# ANEMOMETRO_REED_SWITCH.net
KiCad netlist of a schematic drawn in EAGLE
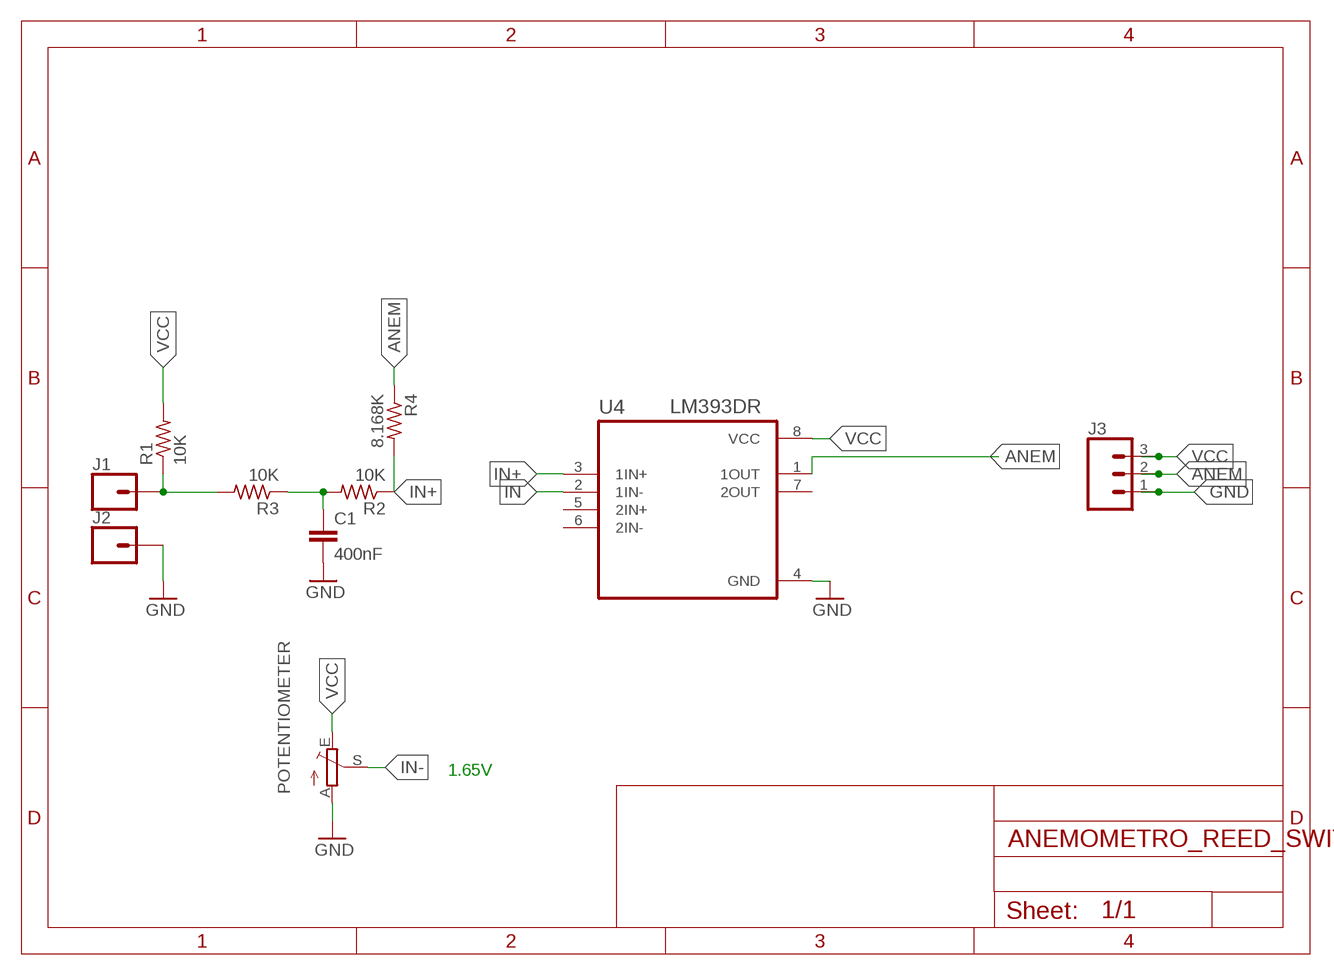
[diagram p0: schematic, sheet 1]

(export (version "E")
  (design (tool "Eeschema 10.0.6"))
  (components
    (comp (ref "C1")
      (value "400nF")
      (footprint "eagle-import:C0603")
      (libsource (lib "eagle-import") (part "C-EUC0603"))
    )
    (comp (ref "J1")
      (value "CONN_01PTH_NO_SILK_YES_STOP")
      (footprint "eagle-import:1X01_NO_SILK")
      (libsource (lib "eagle-import") (part "CONN_01PTH_NO_SILK_YES_STOP"))
    )
    (comp (ref "J2")
      (value "CONN_01PTH_NO_SILK_YES_STOP")
      (footprint "eagle-import:1X01_NO_SILK")
      (libsource (lib "eagle-import") (part "CONN_01PTH_NO_SILK_YES_STOP"))
    )
    (comp (ref "J3")
      (value "CONN_03JST-PTH-VERT")
      (footprint "eagle-import:JST-3-PTH-VERT")
      (libsource (lib "eagle-import") (part "CONN_03JST-PTH-VERT"))
    )
    (comp (ref "POTENTIOMETER")
      (value "TRIM_EU-S64W")
      (footprint "eagle-import:S64W")
      (libsource (lib "eagle-import") (part "TRIM_EU-S64W"))
    )
    (comp (ref "R1")
      (value "10K")
      (footprint "eagle-import:R0603")
      (libsource (lib "eagle-import") (part "R-US_R0603"))
    )
    (comp (ref "R2")
      (value "10K")
      (footprint "eagle-import:R0603")
      (libsource (lib "eagle-import") (part "R-US_R0603"))
    )
    (comp (ref "R3")
      (value "10K")
      (footprint "eagle-import:R0603")
      (libsource (lib "eagle-import") (part "R-US_R0603"))
    )
    (comp (ref "R4")
      (value "8.168K")
      (footprint "eagle-import:R0603")
      (libsource (lib "eagle-import") (part "R-US_R0603"))
    )
    (comp (ref "U4")
      (value "LM393DR")
      (footprint "eagle-import:SOIC127P599X175-8N")
      (fields (field (name "MF") "Texas Instruments"))
      (libsource (lib "eagle-import") (part "LM393DR"))
    )
  )
  (nets
    (net (code "1") (name "ANEM") (class "Default")
      (node (ref "J3") (pin "2") (pinfunction "2_2") (pintype "passive"))
      (node (ref "R4") (pin "1") (pinfunction "1_1") (pintype "passive"))
      (node (ref "U4") (pin "1") (pinfunction "1OUT_1") (pintype "output"))
    )
    (net (code "2") (name "GND") (class "Default")
      (node (ref "C1") (pin "2") (pinfunction "2_2") (pintype "passive"))
      (node (ref "J2") (pin "1") (pinfunction "1_1") (pintype "passive"))
      (node (ref "J3") (pin "1") (pinfunction "1_1") (pintype "passive"))
      (node (ref "POTENTIOMETER") (pin "A") (pinfunction "A_A") (pintype "passive"))
      (node (ref "U4") (pin "4") (pinfunction "GND_4") (pintype "power_in"))
    )
    (net (code "3") (name "IN") (class "Default")
      (node (ref "U4") (pin "2") (pinfunction "1IN-_2") (pintype "input"))
    )
    (net (code "4") (name "IN+") (class "Default")
      (node (ref "R2") (pin "1") (pinfunction "1_1") (pintype "passive"))
      (node (ref "R4") (pin "2") (pinfunction "2_2") (pintype "passive"))
      (node (ref "U4") (pin "3") (pinfunction "1IN+_3") (pintype "input"))
    )
    (net (code "5") (name "IN-") (class "Default")
      (node (ref "POTENTIOMETER") (pin "S") (pinfunction "S_S") (pintype "passive"))
    )
    (net (code "6") (name "Net-(C1-Pad1)") (class "Default")
      (node (ref "C1") (pin "1") (pinfunction "1_1") (pintype "passive"))
      (node (ref "R2") (pin "2") (pinfunction "2_2") (pintype "passive"))
      (node (ref "R3") (pin "1") (pinfunction "1_1") (pintype "passive"))
    )
    (net (code "7") (name "Net-(J1-Pad1)") (class "Default")
      (node (ref "J1") (pin "1") (pinfunction "1_1") (pintype "passive"))
      (node (ref "R1") (pin "1") (pinfunction "1_1") (pintype "passive"))
      (node (ref "R3") (pin "2") (pinfunction "2_2") (pintype "passive"))
    )
    (net (code "8") (name "VCC") (class "Default")
      (node (ref "J3") (pin "3") (pinfunction "3_3") (pintype "passive"))
      (node (ref "POTENTIOMETER") (pin "E") (pinfunction "E_E") (pintype "passive"))
      (node (ref "R1") (pin "2") (pinfunction "2_2") (pintype "passive"))
      (node (ref "U4") (pin "8") (pinfunction "VCC_8") (pintype "power_in"))
    )
    (net (code "9") (name "unconnected-(U4-2IN+-Pad5)") (class "Default")
      (node (ref "U4") (pin "5") (pinfunction "2IN+_5") (pintype "input"))
    )
    (net (code "10") (name "unconnected-(U4-2IN--Pad6)") (class "Default")
      (node (ref "U4") (pin "6") (pinfunction "2IN-_6") (pintype "input"))
    )
    (net (code "11") (name "unconnected-(U4-2OUT-Pad7)") (class "Default")
      (node (ref "U4") (pin "7") (pinfunction "2OUT_7") (pintype "output"))
    )
  )
)
